# mcu.net
KiCad netlist of a schematic drawn in Altium Designer
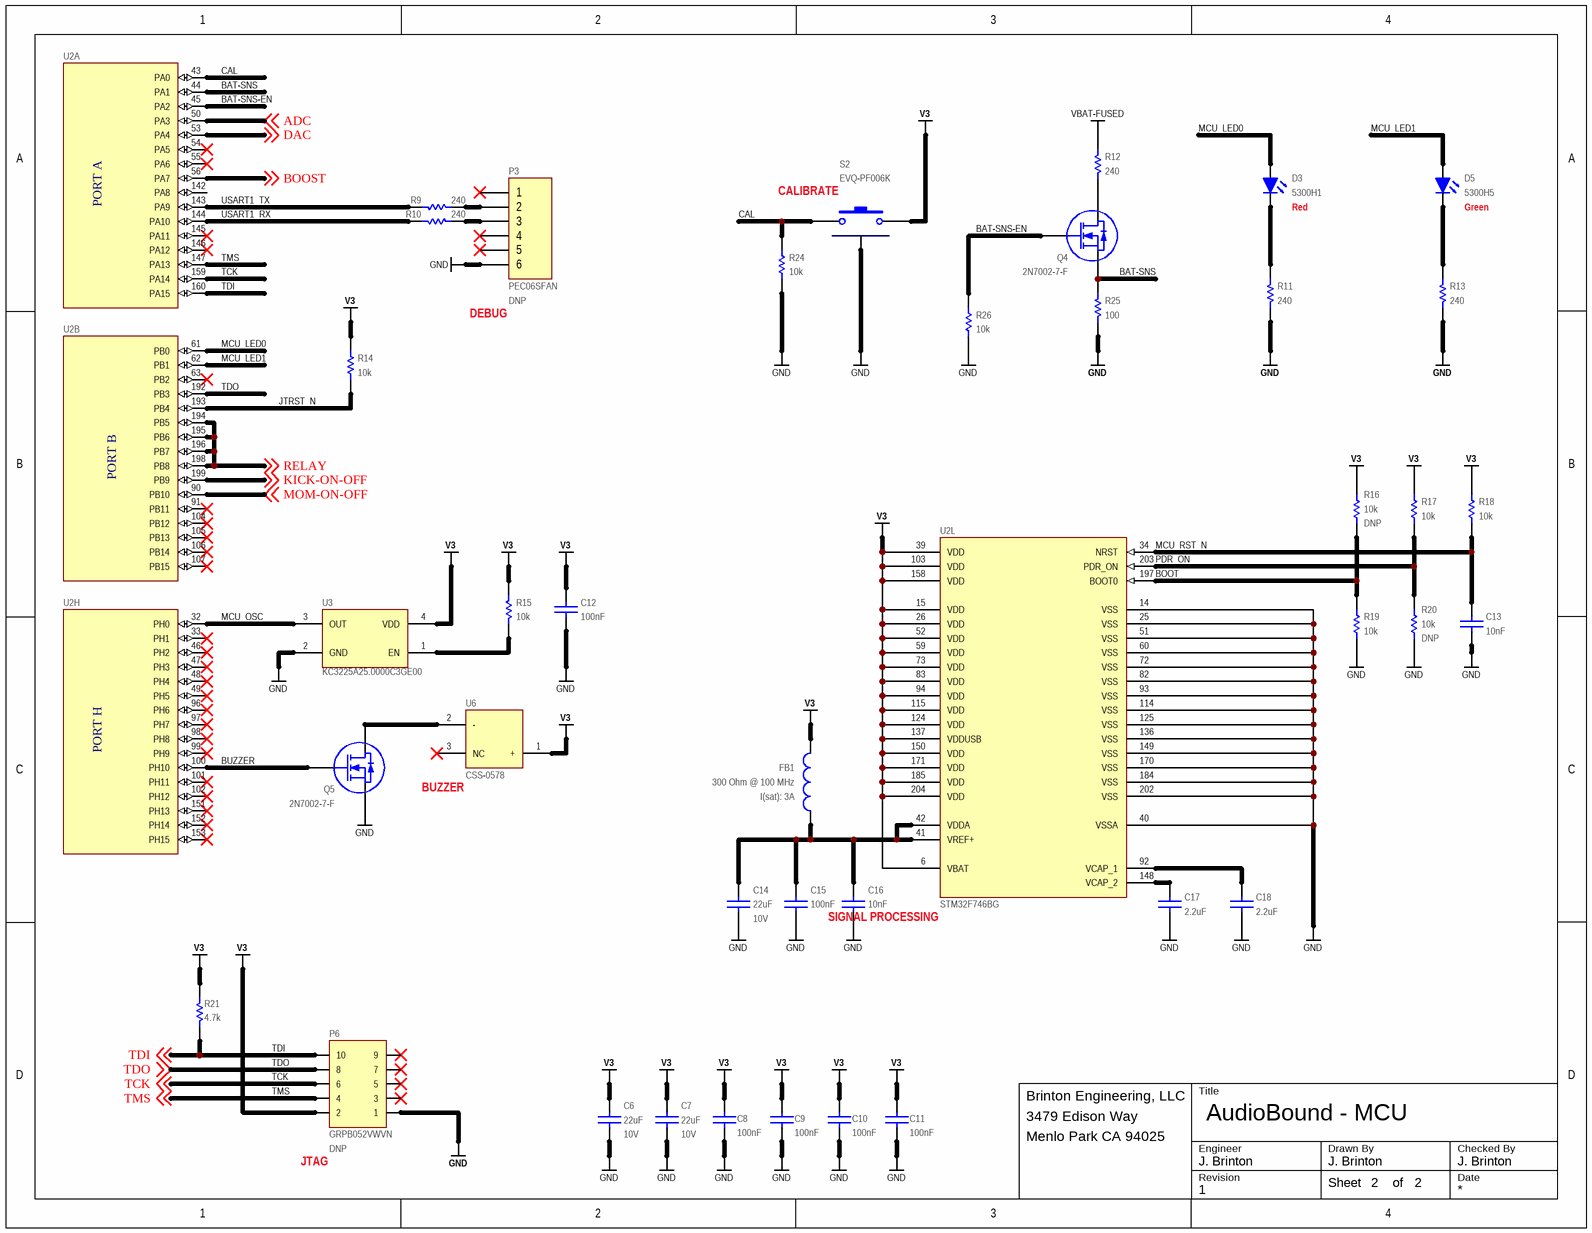
[diagram p0: mcu.SchDoc]

(export (version "E")
  (design (tool "Eeschema 10.0.6"))
  (components
    (comp (ref "C6")
      (value "22uF")
      (footprint "CAPC200X125X145L45N")
      (description "Ceramic Capacitor 22uF ±20% 10V X7S 0805")
      (fields
        (field (name "MANUFACTURER") "TDK")
        (field (name "TOLERANCE") "±20%")
        (field (name "VOLTAGE") "10V")
      )
      (libsource (lib "") (part "CAP_1"))
    )
    (comp (ref "C7")
      (value "22uF")
      (footprint "CAPC200X125X145L45N")
      (description "Ceramic Capacitor 22uF ±20% 10V X7S 0805")
      (fields
        (field (name "MANUFACTURER") "TDK")
        (field (name "TOLERANCE") "±20%")
        (field (name "VOLTAGE") "10V")
      )
      (libsource (lib "") (part "CAP_1"))
    )
    (comp (ref "C8")
      (value "100nF")
      (footprint "CAPC100X50X55L25N")
      (description "Ceramic Capacitor 100nF ±10% 50V X7R 0402")
      (fields (field (name "VOLTAGE") "50V") (field (name "MANUFACTURER") "Murata"))
      (libsource (lib "generic") (part "CAP"))
    )
    (comp (ref "C9")
      (value "100nF")
      (footprint "CAPC100X50X55L25N")
      (description "Ceramic Capacitor 100nF ±10% 50V X7R 0402")
      (fields (field (name "VOLTAGE") "50V") (field (name "MANUFACTURER") "Murata"))
      (libsource (lib "generic") (part "CAP"))
    )
    (comp (ref "C10")
      (value "100nF")
      (footprint "CAPC100X50X55L25N")
      (description "Ceramic Capacitor 100nF ±10% 50V X7R 0402")
      (fields (field (name "VOLTAGE") "50V") (field (name "MANUFACTURER") "Murata"))
      (libsource (lib "generic") (part "CAP"))
    )
    (comp (ref "C11")
      (value "100nF")
      (footprint "CAPC100X50X55L25N")
      (description "Ceramic Capacitor 100nF ±10% 50V X7R 0402")
      (fields (field (name "VOLTAGE") "50V") (field (name "MANUFACTURER") "Murata"))
      (libsource (lib "generic") (part "CAP"))
    )
    (comp (ref "C12")
      (value "100nF")
      (footprint "CAPC100X50X55L25N")
      (description "Ceramic Capacitor 100nF ±10% 50V X7R 0402")
      (fields (field (name "VOLTAGE") "50V") (field (name "MANUFACTURER") "Murata"))
      (libsource (lib "generic") (part "CAP"))
    )
    (comp (ref "C13")
      (value "10nF")
      (footprint "CAPC100X50X55L25N")
      (description "Ceramic Capacitor 10nF ±10% 50V X7R 0402")
      (fields (field (name "TOLERANCE") "±10%") (field (name "MANUFACTURER") "Murata"))
      (libsource (lib "generic") (part "Cap"))
    )
    (comp (ref "C14")
      (value "22uF")
      (footprint "CAPC200X125X145L45N")
      (description "Ceramic Capacitor 22uF ±20% 10V X7S 0805")
      (fields
        (field (name "MANUFACTURER") "TDK")
        (field (name "TOLERANCE") "±20%")
        (field (name "VOLTAGE") "10V")
      )
      (libsource (lib "") (part "CAP_1"))
    )
    (comp (ref "C15")
      (value "100nF")
      (footprint "CAPC100X50X55L25N")
      (description "Ceramic Capacitor 100nF ±10% 50V X7R 0402")
      (fields (field (name "VOLTAGE") "50V") (field (name "MANUFACTURER") "Murata"))
      (libsource (lib "generic") (part "CAP"))
    )
    (comp (ref "C16")
      (value "10nF")
      (footprint "CAPC100X50X55L25N")
      (description "Ceramic Capacitor 10nF ±10% 50V X7R 0402")
      (fields (field (name "TOLERANCE") "±10%") (field (name "MANUFACTURER") "Murata"))
      (libsource (lib "generic") (part "Cap"))
    )
    (comp (ref "C17")
      (value "2.2uF")
      (footprint "CAPC160X80X90L20N")
      (description "Ceramic Capacitor 2.2uF ±20% 10V X7R 0603")
      (fields (field (name "TOLERANCE") "±20%") (field (name "MANUFACTURER") "TDK"))
      (libsource (lib "generic") (part "Cap"))
    )
    (comp (ref "C18")
      (value "2.2uF")
      (footprint "CAPC160X80X90L20N")
      (description "Ceramic Capacitor 2.2uF ±20% 10V X7R 0603")
      (fields (field (name "TOLERANCE") "±20%") (field (name "MANUFACTURER") "TDK"))
      (libsource (lib "generic") (part "Cap"))
    )
    (comp (ref "D3")
      (value "5300H1")
      (footprint "5300Hx")
      (description "LED, Color Red, 10mA, 2.0V")
      (fields (field (name "MANUFACTURER") "Visual Communications Company"))
      (libsource (lib "generic") (part "LED0603RD"))
    )
    (comp (ref "D5")
      (value "5300H5")
      (footprint "5300Hx")
      (description "LED, Color Green, 10mA, 2.2V")
      (fields (field (name "MANUFACTURER") "Visual Communications Company"))
      (libsource (lib "generic") (part "LED0603RD"))
    )
    (comp (ref "FB1")
      (value "300 Ohm @ 100 MHz")
      (footprint "0805")
      (description "Ferrite Chip 300 Ohm @ 100MHz; 3A")
      (fields
        (field (name "MANUFACTURER") "Wurth Electronics, Inc")
        (field (name "I(SAT)") "3A")
        (field (name "Comment") "742792031")
      )
      (libsource (lib "generic") (part "INDUCTOR"))
    )
    (comp (ref "P3")
      (value "PEC06SFAN")
      (footprint "HDR1X6")
      (description "Header, 6-Pin")
      (fields (field (name "MANUFACTURER") "Sullins") (field (name "DO NOT PLACE") "DNP"))
      (libsource (lib "Miscellaneous Connectors") (part "Header 6"))
    )
    (comp (ref "P6")
      (value "GRPB052VWVN")
      (footprint "GRPB052VWVN")
      (description "Male Header, 0.050\" Pitch, 2x5 Position, Right Angle")
      (fields (field (name "MANUFACTURER") "Sullins") (field (name "DO NOT PLACE") "DNP"))
      (libsource (lib "sullins") (part "GRPB052VWVN"))
    )
    (comp (ref "Q4")
      (value "2N7002-7-F")
      (footprint "SOT23")
      (description "N-Channel Enhancement Mode MOSFET")
      (fields (field (name "MANUFACTURER P/N") "2N7002-7-F") (field (name "MANUFACTURER") "Diodes, Inc."))
      (libsource (lib "diodes_inc") (part "2N7002-7-F"))
    )
    (comp (ref "Q5")
      (value "2N7002-7-F")
      (footprint "SOT23")
      (description "N-Channel Enhancement Mode MOSFET")
      (fields (field (name "MANUFACTURER P/N") "2N7002-7-F") (field (name "MANUFACTURER") "Diodes, Inc."))
      (libsource (lib "diodes_inc") (part "2N7002-7-F"))
    )
    (comp (ref "R9")
      (value "240")
      (footprint "RESC1005X40N")
      (description "Thick Film Resistor 240 ±1% 0.1W 75V 0402")
      (fields (field (name "TOLERANCE") "±1%") (field (name "MANUFACTURER") "Panasonic"))
      (libsource (lib "generic") (part "RES"))
    )
    (comp (ref "R10")
      (value "240")
      (footprint "RESC1005X40N")
      (description "Thick Film Resistor 240 ±1% 0.1W 75V 0402")
      (fields (field (name "TOLERANCE") "±1%") (field (name "MANUFACTURER") "Panasonic"))
      (libsource (lib "generic") (part "RES"))
    )
    (comp (ref "R11")
      (value "240")
      (footprint "RESC1005X40N")
      (description "Thick Film Resistor 240 ±1% 0.1W 75V 0402")
      (fields (field (name "TOLERANCE") "±1%") (field (name "MANUFACTURER") "Panasonic"))
      (libsource (lib "generic") (part "RES"))
    )
    (comp (ref "R12")
      (value "240")
      (footprint "RESC1005X40N")
      (description "Thick Film Resistor 240 ±1% 0.1W 75V 0402")
      (fields (field (name "TOLERANCE") "±1%") (field (name "MANUFACTURER") "Panasonic"))
      (libsource (lib "generic") (part "RES"))
    )
    (comp (ref "R13")
      (value "240")
      (footprint "RESC1005X40N")
      (description "Thick Film Resistor 240 ±1% 0.1W 75V 0402")
      (fields (field (name "TOLERANCE") "±1%") (field (name "MANUFACTURER") "Panasonic"))
      (libsource (lib "generic") (part "RES"))
    )
    (comp (ref "R14")
      (value "10k")
      (footprint "RESC1005X40N")
      (description "Thick Film Resistor 10k ±1% 0.1W 50V 0402")
      (fields (field (name "MANUFACTURER") "Panasonic") (field (name "TOLERANCE") "±1%"))
      (libsource (lib "generic") (part "RES"))
    )
    (comp (ref "R15")
      (value "10k")
      (footprint "RESC1005X40N")
      (description "Thick Film Resistor 10k ±1% 0.1W 50V 0402")
      (fields (field (name "MANUFACTURER") "Panasonic") (field (name "TOLERANCE") "±1%"))
      (libsource (lib "generic") (part "RES"))
    )
    (comp (ref "R16")
      (value "10k")
      (footprint "RESC1005X40N")
      (description "Thick Film Resistor 10k ±1% 0.1W 50V 0402")
      (fields
        (field (name "MANUFACTURER") "Panasonic")
        (field (name "TOLERANCE") "±1%")
        (field (name "DO NOT PLACE") "DNP")
      )
      (libsource (lib "generic") (part "RES"))
    )
    (comp (ref "R17")
      (value "10k")
      (footprint "RESC1005X40N")
      (description "Thick Film Resistor 10k ±1% 0.1W 50V 0402")
      (fields (field (name "MANUFACTURER") "Panasonic") (field (name "TOLERANCE") "±1%"))
      (libsource (lib "generic") (part "RES"))
    )
    (comp (ref "R18")
      (value "10k")
      (footprint "RESC1005X40N")
      (description "Thick Film Resistor 10k ±1% 0.1W 50V 0402")
      (fields (field (name "MANUFACTURER") "Panasonic") (field (name "TOLERANCE") "±1%"))
      (libsource (lib "generic") (part "RES"))
    )
    (comp (ref "R19")
      (value "10k")
      (footprint "RESC1005X40N")
      (description "Thick Film Resistor 10k ±1% 0.1W 50V 0402")
      (fields (field (name "MANUFACTURER") "Panasonic") (field (name "TOLERANCE") "±1%"))
      (libsource (lib "generic") (part "RES"))
    )
    (comp (ref "R20")
      (value "10k")
      (footprint "RESC1005X40N")
      (description "Thick Film Resistor 10k ±1% 0.1W 50V 0402")
      (fields
        (field (name "MANUFACTURER") "Panasonic")
        (field (name "TOLERANCE") "±1%")
        (field (name "DO NOT PLACE") "DNP")
      )
      (libsource (lib "generic") (part "RES"))
    )
    (comp (ref "R21")
      (value "4.7k")
      (footprint "RESC1005X40N")
      (description "Thick Film Resistor 4.7k ±1% 0.1W 75V 0402")
      (fields (field (name "TOLERANCE") "±1%") (field (name "MANUFACTURER") "Panasonic"))
      (libsource (lib "generic") (part "RES"))
    )
    (comp (ref "R24")
      (value "10k")
      (footprint "RESC1005X40N")
      (description "Thick Film Resistor 10k ±1% 0.1W 50V 0402")
      (fields (field (name "MANUFACTURER") "Panasonic") (field (name "TOLERANCE") "±1%"))
      (libsource (lib "generic") (part "RES"))
    )
    (comp (ref "R25")
      (value "100")
      (footprint "RESC1005X40N")
      (description "Thick Film Resistor 100 ±1% 0.1W 75V 0402")
      (fields (field (name "TOLERANCE") "±1%") (field (name "MANUFACTURER") "Panasonic"))
      (libsource (lib "generic") (part "RES"))
    )
    (comp (ref "R26")
      (value "10k")
      (footprint "RESC1005X40N")
      (description "Thick Film Resistor 10k ±1% 0.1W 50V 0402")
      (fields (field (name "MANUFACTURER") "Panasonic") (field (name "TOLERANCE") "±1%"))
      (libsource (lib "generic") (part "RES"))
    )
    (comp (ref "S2")
      (value "EVQ-PF006K")
      (footprint "EVQ-PF006K")
      (description "Tactile Switch; Normally Open")
      (fields (field (name "MANUFACTURER") "Panasonic"))
      (libsource (lib "panasonic") (part "EVQ-PF006K"))
    )
    (comp (ref "U2")
      (value "STM32F746BG")
      (footprint "LQFP208")
      (description "STM32 Microcontroller")
      (fields (field (name "MANUFACTURER") "ST Microelectronics"))
      (libsource (lib "hadley") (part "STM32F746BGT6"))
    )
    (comp (ref "U3")
      (value "KC3225A25.0000C3GE00")
      (footprint "OSCCC320X250X80L75X100N")
      (description "Oscillator 25.00Mhz, -+50PPM, 3.3V")
      (fields (field (name "MANUFACTURER") "Kyocera"))
      (libsource (lib "MCD_TOOLS") (part "OSC_25M_NZ2520SB"))
    )
    (comp (ref "U6")
      (value "CSS-0578")
      (footprint "CSS-0578")
      (description "Magnetic Buzzer")
      (fields (field (name "MANUFACTURER") "CUI"))
      (libsource (lib "cui") (part "CSS-0578"))
    )
  )
  (nets
    (net (code "1") (name "/BAT-SNS") (class "Default")
      (node (ref "Q4") (pin "2") (pinfunction "S_2") (pintype "passive"))
      (node (ref "R25") (pin "1") (pinfunction "1_1") (pintype "passive"))
      (node (ref "U2") (pin "44") (pinfunction "PA1_44") (pintype "bidirectional"))
    )
    (net (code "2") (name "/BAT-SNS-EN") (class "Default")
      (node (ref "Q4") (pin "1") (pinfunction "G_1") (pintype "passive"))
      (node (ref "R26") (pin "1") (pinfunction "1_1") (pintype "passive"))
      (node (ref "U2") (pin "45") (pinfunction "PA2_45") (pintype "bidirectional"))
    )
    (net (code "3") (name "/BOOT") (class "Default")
      (node (ref "R16") (pin "1") (pinfunction "1_1") (pintype "passive"))
      (node (ref "R19") (pin "2") (pinfunction "2_2") (pintype "passive"))
      (node (ref "U2") (pin "197") (pinfunction "BOOT0_197") (pintype "input"))
    )
    (net (code "4") (name "/BUZZER") (class "Default")
      (node (ref "Q5") (pin "1") (pinfunction "G_1") (pintype "passive"))
      (node (ref "U2") (pin "100") (pinfunction "PH10_100") (pintype "bidirectional"))
    )
    (net (code "5") (name "/CAL") (class "Default")
      (node (ref "R24") (pin "1") (pinfunction "1_1") (pintype "passive"))
      (node (ref "S2") (pin "1") (pinfunction "1_1") (pintype "passive"))
      (node (ref "U2") (pin "43") (pinfunction "PA0_43") (pintype "bidirectional"))
    )
    (net (code "6") (name "/JTRST_N") (class "Default")
      (node (ref "R14") (pin "1") (pinfunction "1_1") (pintype "passive"))
      (node (ref "U2") (pin "193") (pinfunction "PB4_193") (pintype "bidirectional"))
    )
    (net (code "7") (name "/MCU_LED0") (class "Default")
      (node (ref "D3") (pin "1") (pinfunction "A_1") (pintype "passive"))
      (node (ref "U2") (pin "61") (pinfunction "PB0_61") (pintype "bidirectional"))
    )
    (net (code "8") (name "/MCU_LED1") (class "Default")
      (node (ref "D5") (pin "1") (pinfunction "A_1") (pintype "passive"))
      (node (ref "U2") (pin "62") (pinfunction "PB1_62") (pintype "bidirectional"))
    )
    (net (code "9") (name "/MCU_OSC") (class "Default")
      (node (ref "U2") (pin "32") (pinfunction "PH0_32") (pintype "bidirectional"))
      (node (ref "U3") (pin "3") (pinfunction "OUT_3") (pintype "passive"))
    )
    (net (code "10") (name "/MCU_RST_N") (class "Default")
      (node (ref "C13") (pin "2") (pinfunction "2_2") (pintype "passive"))
      (node (ref "R18") (pin "1") (pinfunction "1_1") (pintype "passive"))
      (node (ref "U2") (pin "34") (pinfunction "NRST_34") (pintype "input"))
    )
    (net (code "11") (name "/PDR_ON") (class "Default")
      (node (ref "R17") (pin "1") (pinfunction "1_1") (pintype "passive"))
      (node (ref "R20") (pin "2") (pinfunction "2_2") (pintype "passive"))
      (node (ref "U2") (pin "203") (pinfunction "PDR_ON_203") (pintype "input"))
    )
    (net (code "12") (name "/USART1_RX") (class "Default")
      (node (ref "R10") (pin "1") (pinfunction "1_1") (pintype "passive"))
      (node (ref "U2") (pin "144") (pinfunction "PA10_144") (pintype "bidirectional"))
    )
    (net (code "13") (name "/USART1_TX") (class "Default")
      (node (ref "R9") (pin "1") (pinfunction "1_1") (pintype "passive"))
      (node (ref "U2") (pin "143") (pinfunction "PA9_143") (pintype "bidirectional"))
    )
    (net (code "14") (name "ADC") (class "Default")
      (node (ref "U2") (pin "50") (pinfunction "PA3_50") (pintype "bidirectional"))
    )
    (net (code "15") (name "BOOST") (class "Default")
      (node (ref "U2") (pin "56") (pinfunction "PA7_56") (pintype "bidirectional"))
    )
    (net (code "16") (name "DAC") (class "Default")
      (node (ref "U2") (pin "53") (pinfunction "PA4_53") (pintype "bidirectional"))
    )
    (net (code "17") (name "GND") (class "Default")
      (node (ref "C10") (pin "1") (pinfunction "1_1") (pintype "passive"))
      (node (ref "C11") (pin "1") (pinfunction "1_1") (pintype "passive"))
      (node (ref "C12") (pin "1") (pinfunction "1_1") (pintype "passive"))
      (node (ref "C13") (pin "1") (pinfunction "1_1") (pintype "passive"))
      (node (ref "C14") (pin "2") (pinfunction "2_2") (pintype "passive"))
      (node (ref "C15") (pin "1") (pinfunction "1_1") (pintype "passive"))
      (node (ref "C16") (pin "1") (pinfunction "1_1") (pintype "passive"))
      (node (ref "C17") (pin "1") (pinfunction "1_1") (pintype "passive"))
      (node (ref "C18") (pin "1") (pinfunction "1_1") (pintype "passive"))
      (node (ref "C6") (pin "2") (pinfunction "2_2") (pintype "passive"))
      (node (ref "C7") (pin "2") (pinfunction "2_2") (pintype "passive"))
      (node (ref "C8") (pin "1") (pinfunction "1_1") (pintype "passive"))
      (node (ref "C9") (pin "1") (pinfunction "1_1") (pintype "passive"))
      (node (ref "P3") (pin "6") (pinfunction "6_6") (pintype "passive"))
      (node (ref "P6") (pin "1") (pinfunction "1_1") (pintype "passive"))
      (node (ref "Q5") (pin "2") (pinfunction "S_2") (pintype "passive"))
      (node (ref "R11") (pin "2") (pinfunction "2_2") (pintype "passive"))
      (node (ref "R13") (pin "2") (pinfunction "2_2") (pintype "passive"))
      (node (ref "R19") (pin "1") (pinfunction "1_1") (pintype "passive"))
      (node (ref "R20") (pin "1") (pinfunction "1_1") (pintype "passive"))
      (node (ref "R24") (pin "2") (pinfunction "2_2") (pintype "passive"))
      (node (ref "R25") (pin "2") (pinfunction "2_2") (pintype "passive"))
      (node (ref "R26") (pin "2") (pinfunction "2_2") (pintype "passive"))
      (node (ref "S2") (pin "3") (pinfunction "3_3") (pintype "passive"))
      (node (ref "U2") (pin "114") (pinfunction "VSS_114") (pintype "power_in"))
      (node (ref "U2") (pin "125") (pinfunction "VSS_125") (pintype "power_in"))
      (node (ref "U2") (pin "136") (pinfunction "VSS_136") (pintype "power_in"))
      (node (ref "U2") (pin "14") (pinfunction "VSS_14") (pintype "power_in"))
      (node (ref "U2") (pin "149") (pinfunction "VSS_149") (pintype "power_in"))
      (node (ref "U2") (pin "170") (pinfunction "VSS_170") (pintype "power_in"))
      (node (ref "U2") (pin "184") (pinfunction "VSS_184") (pintype "power_in"))
      (node (ref "U2") (pin "202") (pinfunction "VSS_202") (pintype "power_in"))
      (node (ref "U2") (pin "25") (pinfunction "VSS_25") (pintype "power_in"))
      (node (ref "U2") (pin "40") (pinfunction "VSSA_40") (pintype "power_in"))
      (node (ref "U2") (pin "51") (pinfunction "VSS_51") (pintype "power_in"))
      (node (ref "U2") (pin "60") (pinfunction "VSS_60") (pintype "power_in"))
      (node (ref "U2") (pin "72") (pinfunction "VSS_72") (pintype "power_in"))
      (node (ref "U2") (pin "82") (pinfunction "VSS_82") (pintype "power_in"))
      (node (ref "U2") (pin "93") (pinfunction "VSS_93") (pintype "power_in"))
      (node (ref "U3") (pin "2") (pinfunction "GND_2") (pintype "passive"))
    )
    (net (code "18") (name "KICK-ON-OFF") (class "Default")
      (node (ref "U2") (pin "199") (pinfunction "PB9_199") (pintype "bidirectional"))
    )
    (net (code "19") (name "MOM-ON-OFF") (class "Default")
      (node (ref "U2") (pin "90") (pinfunction "PB10_90") (pintype "bidirectional"))
    )
    (net (code "20") (name "Net-(D3-K)") (class "Default")
      (node (ref "D3") (pin "2") (pinfunction "K_2") (pintype "passive"))
      (node (ref "R11") (pin "1") (pinfunction "1_1") (pintype "passive"))
    )
    (net (code "21") (name "Net-(D5-K)") (class "Default")
      (node (ref "D5") (pin "2") (pinfunction "K_2") (pintype "passive"))
      (node (ref "R13") (pin "1") (pinfunction "1_1") (pintype "passive"))
    )
    (net (code "22") (name "Net-(P3-Pad2)") (class "Default")
      (node (ref "P3") (pin "2") (pinfunction "2_2") (pintype "passive"))
      (node (ref "R9") (pin "2") (pinfunction "2_2") (pintype "passive"))
    )
    (net (code "23") (name "Net-(P3-Pad3)") (class "Default")
      (node (ref "P3") (pin "3") (pinfunction "3_3") (pintype "passive"))
      (node (ref "R10") (pin "2") (pinfunction "2_2") (pintype "passive"))
    )
    (net (code "24") (name "Net-(Q4-D)") (class "Default")
      (node (ref "Q4") (pin "3") (pinfunction "D_3") (pintype "passive"))
      (node (ref "R12") (pin "2") (pinfunction "2_2") (pintype "passive"))
    )
    (net (code "25") (name "Net-(Q5-D)") (class "Default")
      (node (ref "Q5") (pin "3") (pinfunction "D_3") (pintype "passive"))
      (node (ref "U6") (pin "2") (pinfunction "-_2") (pintype "passive"))
    )
    (net (code "26") (name "Net-(U2L-VCAP_1)") (class "Default")
      (node (ref "C18") (pin "2") (pinfunction "2_2") (pintype "passive"))
      (node (ref "U2") (pin "92") (pinfunction "VCAP_1_92") (pintype "power_in"))
    )
    (net (code "27") (name "Net-(U2L-VCAP_2)") (class "Default")
      (node (ref "C17") (pin "2") (pinfunction "2_2") (pintype "passive"))
      (node (ref "U2") (pin "148") (pinfunction "VCAP_2_148") (pintype "power_in"))
    )
    (net (code "28") (name "Net-(U2L-VDDA)") (class "Default")
      (node (ref "C14") (pin "1") (pinfunction "1_1") (pintype "passive"))
      (node (ref "C15") (pin "2") (pinfunction "2_2") (pintype "passive"))
      (node (ref "C16") (pin "2") (pinfunction "2_2") (pintype "passive"))
      (node (ref "FB1") (pin "1") (pinfunction "1_1") (pintype "passive"))
      (node (ref "U2") (pin "41") (pinfunction "VREF+_41") (pintype "power_in"))
      (node (ref "U2") (pin "42") (pinfunction "VDDA_42") (pintype "power_in"))
    )
    (net (code "29") (name "Net-(U3-EN)") (class "Default")
      (node (ref "R15") (pin "1") (pinfunction "1_1") (pintype "passive"))
      (node (ref "U3") (pin "1") (pinfunction "EN_1") (pintype "passive"))
    )
    (net (code "30") (name "RELAY") (class "Default")
      (node (ref "U2") (pin "194") (pinfunction "PB5_194") (pintype "bidirectional"))
      (node (ref "U2") (pin "195") (pinfunction "PB6_195") (pintype "bidirectional"))
      (node (ref "U2") (pin "196") (pinfunction "PB7_196") (pintype "bidirectional"))
      (node (ref "U2") (pin "198") (pinfunction "PB8_198") (pintype "bidirectional"))
    )
    (net (code "31") (name "TCK") (class "Default")
      (node (ref "P6") (pin "6") (pinfunction "6_6") (pintype "passive"))
      (node (ref "U2") (pin "159") (pinfunction "PA14_159") (pintype "bidirectional"))
    )
    (net (code "32") (name "TDI") (class "Default")
      (node (ref "P6") (pin "10") (pinfunction "10_10") (pintype "passive"))
      (node (ref "R21") (pin "1") (pinfunction "1_1") (pintype "passive"))
      (node (ref "U2") (pin "160") (pinfunction "PA15_160") (pintype "bidirectional"))
    )
    (net (code "33") (name "TDO") (class "Default")
      (node (ref "P6") (pin "8") (pinfunction "8_8") (pintype "passive"))
      (node (ref "U2") (pin "192") (pinfunction "PB3_192") (pintype "bidirectional"))
    )
    (net (code "34") (name "TMS") (class "Default")
      (node (ref "P6") (pin "4") (pinfunction "4_4") (pintype "passive"))
      (node (ref "U2") (pin "147") (pinfunction "PA13_147") (pintype "bidirectional"))
    )
    (net (code "35") (name "V3") (class "Default")
      (node (ref "C10") (pin "2") (pinfunction "2_2") (pintype "passive"))
      (node (ref "C11") (pin "2") (pinfunction "2_2") (pintype "passive"))
      (node (ref "C12") (pin "2") (pinfunction "2_2") (pintype "passive"))
      (node (ref "C6") (pin "1") (pinfunction "1_1") (pintype "passive"))
      (node (ref "C7") (pin "1") (pinfunction "1_1") (pintype "passive"))
      (node (ref "C8") (pin "2") (pinfunction "2_2") (pintype "passive"))
      (node (ref "C9") (pin "2") (pinfunction "2_2") (pintype "passive"))
      (node (ref "FB1") (pin "2") (pinfunction "2_2") (pintype "passive"))
      (node (ref "P6") (pin "2") (pinfunction "2_2") (pintype "passive"))
      (node (ref "R14") (pin "2") (pinfunction "2_2") (pintype "passive"))
      (node (ref "R15") (pin "2") (pinfunction "2_2") (pintype "passive"))
      (node (ref "R16") (pin "2") (pinfunction "2_2") (pintype "passive"))
      (node (ref "R17") (pin "2") (pinfunction "2_2") (pintype "passive"))
      (node (ref "R18") (pin "2") (pinfunction "2_2") (pintype "passive"))
      (node (ref "R21") (pin "2") (pinfunction "2_2") (pintype "passive"))
      (node (ref "S2") (pin "2") (pinfunction "2_2") (pintype "passive"))
      (node (ref "U2") (pin "103") (pinfunction "VDD_103") (pintype "power_in"))
      (node (ref "U2") (pin "115") (pinfunction "VDD_115") (pintype "power_in"))
      (node (ref "U2") (pin "124") (pinfunction "VDD_124") (pintype "power_in"))
      (node (ref "U2") (pin "137") (pinfunction "VDDUSB_137") (pintype "power_in"))
      (node (ref "U2") (pin "15") (pinfunction "VDD_15") (pintype "power_in"))
      (node (ref "U2") (pin "150") (pinfunction "VDD_150") (pintype "power_in"))
      (node (ref "U2") (pin "158") (pinfunction "VDD_158") (pintype "power_in"))
      (node (ref "U2") (pin "171") (pinfunction "VDD_171") (pintype "power_in"))
      (node (ref "U2") (pin "185") (pinfunction "VDD_185") (pintype "power_in"))
      (node (ref "U2") (pin "204") (pinfunction "VDD_204") (pintype "power_in"))
      (node (ref "U2") (pin "26") (pinfunction "VDD_26") (pintype "power_in"))
      (node (ref "U2") (pin "39") (pinfunction "VDD_39") (pintype "power_in"))
      (node (ref "U2") (pin "52") (pinfunction "VDD_52") (pintype "power_in"))
      (node (ref "U2") (pin "59") (pinfunction "VDD_59") (pintype "power_in"))
      (node (ref "U2") (pin "6") (pinfunction "VBAT_6") (pintype "power_in"))
      (node (ref "U2") (pin "73") (pinfunction "VDD_73") (pintype "power_in"))
      (node (ref "U2") (pin "83") (pinfunction "VDD_83") (pintype "power_in"))
      (node (ref "U2") (pin "94") (pinfunction "VDD_94") (pintype "power_in"))
      (node (ref "U3") (pin "4") (pinfunction "VDD_4") (pintype "passive"))
      (node (ref "U6") (pin "1") (pinfunction "+_1") (pintype "passive"))
    )
    (net (code "36") (name "VBAT-FUSED") (class "Default")
      (node (ref "R12") (pin "1") (pinfunction "1_1") (pintype "passive"))
    )
    (net (code "37") (name "unconnected-(P3-Pad1)") (class "Default")
      (node (ref "P3") (pin "1") (pinfunction "1_1") (pintype "passive+no_connect"))
    )
    (net (code "38") (name "unconnected-(P3-Pad4)") (class "Default")
      (node (ref "P3") (pin "4") (pinfunction "4_4") (pintype "passive+no_connect"))
    )
    (net (code "39") (name "unconnected-(P3-Pad5)") (class "Default")
      (node (ref "P3") (pin "5") (pinfunction "5_5") (pintype "passive+no_connect"))
    )
    (net (code "40") (name "unconnected-(P6-Pad3)") (class "Default")
      (node (ref "P6") (pin "3") (pinfunction "3_3") (pintype "passive+no_connect"))
    )
    (net (code "41") (name "unconnected-(P6-Pad5)") (class "Default")
      (node (ref "P6") (pin "5") (pinfunction "5_5") (pintype "passive+no_connect"))
    )
    (net (code "42") (name "unconnected-(P6-Pad7)") (class "Default")
      (node (ref "P6") (pin "7") (pinfunction "7_7") (pintype "passive+no_connect"))
    )
    (net (code "43") (name "unconnected-(P6-Pad9)") (class "Default")
      (node (ref "P6") (pin "9") (pinfunction "9_9") (pintype "passive+no_connect"))
    )
    (net (code "44") (name "unconnected-(U2A-PA5-Pad54)") (class "Default")
      (node (ref "U2") (pin "54") (pinfunction "PA5_54") (pintype "bidirectional+no_connect"))
    )
    (net (code "45") (name "unconnected-(U2A-PA6-Pad55)") (class "Default")
      (node (ref "U2") (pin "55") (pinfunction "PA6_55") (pintype "bidirectional+no_connect"))
    )
    (net (code "46") (name "unconnected-(U2A-PA8-Pad142)") (class "Default")
      (node (ref "U2") (pin "142") (pinfunction "PA8_142") (pintype "bidirectional"))
    )
    (net (code "47") (name "unconnected-(U2A-PA11-Pad145)") (class "Default")
      (node (ref "U2") (pin "145") (pinfunction "PA11_145") (pintype "bidirectional+no_connect"))
    )
    (net (code "48") (name "unconnected-(U2A-PA12-Pad146)") (class "Default")
      (node (ref "U2") (pin "146") (pinfunction "PA12_146") (pintype "bidirectional+no_connect"))
    )
    (net (code "49") (name "unconnected-(U2B-PB2-Pad63)") (class "Default")
      (node (ref "U2") (pin "63") (pinfunction "PB2_63") (pintype "bidirectional+no_connect"))
    )
    (net (code "50") (name "unconnected-(U2B-PB11-Pad91)") (class "Default")
      (node (ref "U2") (pin "91") (pinfunction "PB11_91") (pintype "bidirectional+no_connect"))
    )
    (net (code "51") (name "unconnected-(U2B-PB12-Pad104)") (class "Default")
      (node (ref "U2") (pin "104") (pinfunction "PB12_104") (pintype "bidirectional+no_connect"))
    )
    (net (code "52") (name "unconnected-(U2B-PB13-Pad105)") (class "Default")
      (node (ref "U2") (pin "105") (pinfunction "PB13_105") (pintype "bidirectional+no_connect"))
    )
    (net (code "53") (name "unconnected-(U2B-PB14-Pad106)") (class "Default")
      (node (ref "U2") (pin "106") (pinfunction "PB14_106") (pintype "bidirectional+no_connect"))
    )
    (net (code "54") (name "unconnected-(U2B-PB15-Pad107)") (class "Default")
      (node (ref "U2") (pin "107") (pinfunction "PB15_107") (pintype "bidirectional+no_connect"))
    )
    (net (code "55") (name "unconnected-(U2H-PH1-Pad33)") (class "Default")
      (node (ref "U2") (pin "33") (pinfunction "PH1_33") (pintype "bidirectional+no_connect"))
    )
    (net (code "56") (name "unconnected-(U2H-PH2-Pad46)") (class "Default")
      (node (ref "U2") (pin "46") (pinfunction "PH2_46") (pintype "bidirectional+no_connect"))
    )
    (net (code "57") (name "unconnected-(U2H-PH3-Pad47)") (class "Default")
      (node (ref "U2") (pin "47") (pinfunction "PH3_47") (pintype "bidirectional+no_connect"))
    )
    (net (code "58") (name "unconnected-(U2H-PH4-Pad48)") (class "Default")
      (node (ref "U2") (pin "48") (pinfunction "PH4_48") (pintype "bidirectional+no_connect"))
    )
    (net (code "59") (name "unconnected-(U2H-PH5-Pad49)") (class "Default")
      (node (ref "U2") (pin "49") (pinfunction "PH5_49") (pintype "bidirectional+no_connect"))
    )
    (net (code "60") (name "unconnected-(U2H-PH6-Pad96)") (class "Default")
      (node (ref "U2") (pin "96") (pinfunction "PH6_96") (pintype "bidirectional+no_connect"))
    )
    (net (code "61") (name "unconnected-(U2H-PH7-Pad97)") (class "Default")
      (node (ref "U2") (pin "97") (pinfunction "PH7_97") (pintype "bidirectional+no_connect"))
    )
    (net (code "62") (name "unconnected-(U2H-PH8-Pad98)") (class "Default")
      (node (ref "U2") (pin "98") (pinfunction "PH8_98") (pintype "bidirectional+no_connect"))
    )
    (net (code "63") (name "unconnected-(U2H-PH9-Pad99)") (class "Default")
      (node (ref "U2") (pin "99") (pinfunction "PH9_99") (pintype "bidirectional+no_connect"))
    )
    (net (code "64") (name "unconnected-(U2H-PH11-Pad101)") (class "Default")
      (node (ref "U2") (pin "101") (pinfunction "PH11_101") (pintype "bidirectional+no_connect"))
    )
    (net (code "65") (name "unconnected-(U2H-PH12-Pad102)") (class "Default")
      (node (ref "U2") (pin "102") (pinfunction "PH12_102") (pintype "bidirectional+no_connect"))
    )
    (net (code "66") (name "unconnected-(U2H-PH13-Pad151)") (class "Default")
      (node (ref "U2") (pin "151") (pinfunction "PH13_151") (pintype "bidirectional+no_connect"))
    )
    (net (code "67") (name "unconnected-(U2H-PH14-Pad152)") (class "Default")
      (node (ref "U2") (pin "152") (pinfunction "PH14_152") (pintype "bidirectional+no_connect"))
    )
    (net (code "68") (name "unconnected-(U2H-PH15-Pad153)") (class "Default")
      (node (ref "U2") (pin "153") (pinfunction "PH15_153") (pintype "bidirectional+no_connect"))
    )
    (net (code "69") (name "unconnected-(U6-NC-Pad3)") (class "Default")
      (node (ref "U6") (pin "3") (pinfunction "NC_3") (pintype "passive+no_connect"))
    )
  )
)
